# esp32-hanover-flipdot.net
KiCad netlist of a schematic drawn in EAGLE
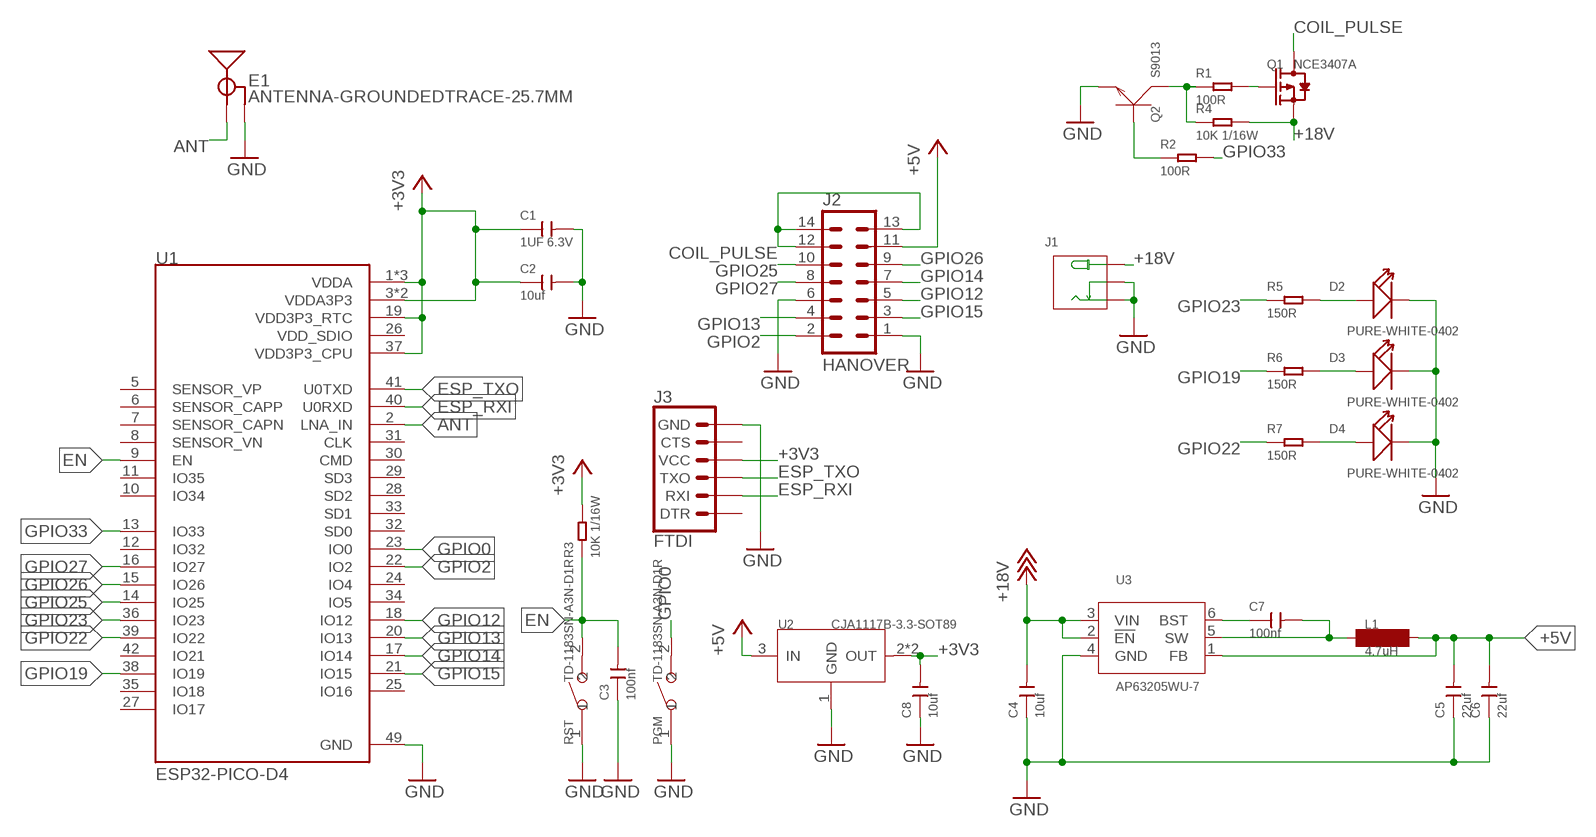
[diagram p0: schematic, sheet 1]

(export (version "E")
  (design (tool "Eeschema 10.0.6"))
  (components
    (comp (ref "C1")
      (value "1UF 6.3V")
      (footprint "eagle-import:C0402")
      (fields (field (name "MPN") "CC0402KRX5R5BB105"))
      (libsource (lib "eagle-import") (part "CERAMIC-1UF-6.3V-10%-X5R(0402)"))
    )
    (comp (ref "C2")
      (value "10uf")
      (footprint "eagle-import:C0402")
      (fields (field (name "MPN") "CC0402MRX5R5BB106"))
      (libsource (lib "eagle-import") (part "CERAMIC-10UF-6.3V-20%-X5R(0402)"))
    )
    (comp (ref "C3")
      (value "100nf")
      (footprint "eagle-import:C0402")
      (fields (field (name "MPN") "CC0402KRX7R8BB104"))
      (libsource (lib "eagle-import") (part "CERAMIC-100NF-25V-10%-X7R(0402)"))
    )
    (comp (ref "C4")
      (value "10uf")
      (footprint "eagle-import:C0805")
      (fields (field (name "MPN") "CC0805KKX5R8BB106"))
      (libsource (lib "eagle-import") (part "CERAMIC-10UF-25V-10%-X5R(0805)"))
    )
    (comp (ref "C5")
      (value "22uf")
      (footprint "eagle-import:C0805")
      (fields (field (name "MPN") "CC0805MKX5R5BB226"))
      (libsource (lib "eagle-import") (part "CERAMIC-22UF-6.3V-20%-X5R(0805)"))
    )
    (comp (ref "C6")
      (value "22uf")
      (footprint "eagle-import:C0805")
      (fields (field (name "MPN") "CC0805MKX5R5BB226"))
      (libsource (lib "eagle-import") (part "CERAMIC-22UF-6.3V-20%-X5R(0805)"))
    )
    (comp (ref "C7")
      (value "100nf")
      (footprint "eagle-import:C0402")
      (fields (field (name "MPN") "CC0402KRX7R8BB104"))
      (libsource (lib "eagle-import") (part "CERAMIC-100NF-25V-10%-X7R(0402)"))
    )
    (comp (ref "C8")
      (value "10uf")
      (footprint "eagle-import:C0402")
      (fields (field (name "MPN") "CC0402MRX5R5BB106"))
      (libsource (lib "eagle-import") (part "CERAMIC-10UF-6.3V-20%-X5R(0402)"))
    )
    (comp (ref "D2")
      (value "PURE-WHITE-0402")
      (footprint "eagle-import:LED-0402")
      (fields (field (name "MPN") "16-219A/T2D-AR2T1QY/3T"))
      (libsource (lib "eagle-import") (part "SMD-LED-YELLOW-DIFFUSED-PURE-WHITE(0402)"))
    )
    (comp (ref "D3")
      (value "PURE-WHITE-0402")
      (footprint "eagle-import:LED-0402")
      (fields (field (name "MPN") "16-219A/T2D-AR2T1QY/3T"))
      (libsource (lib "eagle-import") (part "SMD-LED-YELLOW-DIFFUSED-PURE-WHITE(0402)"))
    )
    (comp (ref "D4")
      (value "PURE-WHITE-0402")
      (footprint "eagle-import:LED-0402")
      (fields (field (name "MPN") "16-219A/T2D-AR2T1QY/3T"))
      (libsource (lib "eagle-import") (part "SMD-LED-YELLOW-DIFFUSED-PURE-WHITE(0402)"))
    )
    (comp (ref "E1")
      (value "ANTENNA-GROUNDEDTRACE-25.7MM")
      (footprint "eagle-import:TRACE_ANTENNA_2.4GHZ_25.7MM")
      (libsource (lib "eagle-import") (part "ANTENNA-GROUNDEDTRACE-25.7MM"))
    )
    (comp (ref "J1")
      (value "DC-005")
      (footprint "eagle-import:3P-L14.2_W11.0_H9.0MM")
      (libsource (lib "eagle-import") (part "JACK-DC-005'DC-005'"))
    )
    (comp (ref "J2")
      (value "HANOVER")
      (footprint "eagle-import:ML14")
      (libsource (lib "eagle-import") (part "ML14"))
    )
    (comp (ref "J3")
      (value "FTDI")
      (footprint "eagle-import:6_PIN_SERIAL_TARGET_SIDE_W_SILK")
      (libsource (lib "eagle-import") (part "6_PIN_SERIAL_TARGETSILK"))
    )
    (comp (ref "L1")
      (value "4.7uH")
      (footprint "eagle-import:INDC2016X100N")
      (fields (field (name "TOLERANCE") "20%"))
      (libsource (lib "eagle-import") (part "VLS201610HBX-4R7M-1"))
    )
    (comp (ref "PGM")
      (value "TD-1183SN-A3N-D1R")
      (footprint "eagle-import:SW2-2.6-3.0X2.5X1.2+0.4MM")
      (fields (field (name "MPN") "B3U-1000P-2P-SMD"))
      (libsource (lib "eagle-import") (part "SMD-BUTTON(2P-3.0X2.5X1.2+0.4MM)-B3U-1000P-2P-SMD"))
    )
    (comp (ref "Q1")
      (value "NCE3407A")
      (footprint "eagle-import:SOT-23")
      (libsource (lib "eagle-import") (part "SMD-MOSFET-P-CH-VDC=30V-ID=4.3A-NCE3407A(SOT-23)"))
    )
    (comp (ref "Q2")
      (value "S9013")
      (footprint "eagle-import:SOT-23")
      (libsource (lib "eagle-import") (part "SMD-TRANSISTORS-NPN-25V-500MA-S9013(SOT-23)"))
    )
    (comp (ref "R1")
      (value "100R")
      (footprint "eagle-import:R0402")
      (fields (field (name "MPN") "RC0402JR-07100RL"))
      (libsource (lib "eagle-import") (part "SMD-RES-100R-5%-1/16W(0402)"))
    )
    (comp (ref "R2")
      (value "100R")
      (footprint "eagle-import:R0402")
      (fields (field (name "MPN") "RC0402JR-07100RL"))
      (libsource (lib "eagle-import") (part "SMD-RES-100R-5%-1/16W(0402)"))
    )
    (comp (ref "R3")
      (value "10K 1/16W")
      (footprint "eagle-import:R0402")
      (fields (field (name "MPN") "RC0402FR-0710KL"))
      (libsource (lib "eagle-import") (part "SMD-RES-10K-1%-1/16W(0402)"))
    )
    (comp (ref "R4")
      (value "10K 1/16W")
      (footprint "eagle-import:R0402")
      (fields (field (name "MPN") "RC0402FR-0710KL"))
      (libsource (lib "eagle-import") (part "SMD-RES-10K-1%-1/16W(0402)"))
    )
    (comp (ref "R5")
      (value "150R")
      (footprint "eagle-import:R0402")
      (fields (field (name "MPN") "RC0402JR-070RL") (field (name "MPN_1") "RC0402FR-07150RL"))
      (libsource (lib "eagle-import") (part "SMD-RES-150R-1%-1/16W(0402)"))
    )
    (comp (ref "R6")
      (value "150R")
      (footprint "eagle-import:R0402")
      (fields (field (name "MPN") "RC0402JR-070RL") (field (name "MPN_1") "RC0402FR-07150RL"))
      (libsource (lib "eagle-import") (part "SMD-RES-150R-1%-1/16W(0402)"))
    )
    (comp (ref "R7")
      (value "150R")
      (footprint "eagle-import:R0402")
      (fields (field (name "MPN") "RC0402JR-070RL") (field (name "MPN_1") "RC0402FR-07150RL"))
      (libsource (lib "eagle-import") (part "SMD-RES-150R-1%-1/16W(0402)"))
    )
    (comp (ref "RST")
      (value "TD-1183SN-A3N-D1R")
      (footprint "eagle-import:SW2-2.6-3.0X2.5X1.2+0.4MM")
      (fields (field (name "MPN") "B3U-1000P-2P-SMD"))
      (libsource (lib "eagle-import") (part "SMD-BUTTON(2P-3.0X2.5X1.2+0.4MM)-B3U-1000P-2P-SMD"))
    )
    (comp (ref "U1")
      (value "ESP32-PICO-D4")
      (footprint "eagle-import:PQFN50P700X700X104-49N")
      (fields (field (name "MF") "Espressif Systems"))
      (libsource (lib "eagle-import") (part "ESP32-PICO-D4"))
    )
    (comp (ref "U2")
      (value "CJA1117B-3.3-SOT89")
      (footprint "eagle-import:SOT-89")
      (fields (field (name "MPN") "CJA1117B-3.3"))
      (libsource (lib "eagle-import") (part "PMIC-CJA1117B-3.3(SOT-89)"))
    )
    (comp (ref "U3")
      (value "AP63205WU-7")
      (footprint "eagle-import:SOT95P280X100-6N")
      (libsource (lib "eagle-import") (part "AP63205WU-7"))
    )
  )
  (nets
    (net (code "1") (name "+3V3") (class "Default")
      (node (ref "C1") (pin "1") (pinfunction "1_1") (pintype "passive"))
      (node (ref "C2") (pin "1") (pinfunction "1_1") (pintype "passive"))
      (node (ref "C8") (pin "2") (pinfunction "2_2") (pintype "passive"))
      (node (ref "J3") (pin "P$4") (pinfunction "VCC_P$4") (pintype "passive"))
      (node (ref "R3") (pin "2") (pinfunction "2_2") (pintype "passive"))
      (node (ref "U1") (pin "1") (pinfunction "VDDA_1") (pintype "power_in"))
      (node (ref "U1") (pin "19") (pinfunction "VDD3P3_RTC_19") (pintype "power_in"))
      (node (ref "U1") (pin "3") (pinfunction "VDDA3P3_3") (pintype "power_in"))
      (node (ref "U1") (pin "37") (pinfunction "VDD3P3_CPU_37") (pintype "power_in"))
      (node (ref "U1") (pin "4") (pinfunction "VDDA3P3_4") (pintype "power_in"))
      (node (ref "U1") (pin "43") (pinfunction "VDDA_43") (pintype "power_in"))
      (node (ref "U1") (pin "46") (pinfunction "VDDA_46") (pintype "power_in"))
      (node (ref "U2") (pin "2") (pinfunction "OUT_2") (pintype "bidirectional"))
      (node (ref "U2") (pin "4") (pinfunction "OUT_4") (pintype "bidirectional"))
    )
    (net (code "2") (name "+5V") (class "Default")
      (node (ref "C5") (pin "2") (pinfunction "2_2") (pintype "passive"))
      (node (ref "C6") (pin "2") (pinfunction "2_2") (pintype "passive"))
      (node (ref "J2") (pin "11") (pinfunction "11_11") (pintype "passive"))
      (node (ref "L1") (pin "2") (pinfunction "2_2") (pintype "passive"))
      (node (ref "U2") (pin "3") (pinfunction "IN_3") (pintype "bidirectional"))
      (node (ref "U3") (pin "1") (pinfunction "FB_1") (pintype "power_in"))
    )
    (net (code "3") (name "+18V") (class "Default")
      (node (ref "C4") (pin "2") (pinfunction "2_2") (pintype "passive"))
      (node (ref "J1") (pin "+B") (pinfunction "+_+B") (pintype "bidirectional"))
      (node (ref "J1") (pin "+T") (pinfunction "+_+T") (pintype "bidirectional"))
      (node (ref "Q1") (pin "2") (pinfunction "S_2") (pintype "passive"))
      (node (ref "R4") (pin "2") (pinfunction "2_2") (pintype "passive"))
      (node (ref "U3") (pin "2") (pinfunction "~{EN}_2") (pintype "input"))
      (node (ref "U3") (pin "3") (pinfunction "VIN_3") (pintype "power_in"))
    )
    (net (code "4") (name "/COIL_PULSE") (class "Default")
      (node (ref "J2") (pin "12") (pinfunction "12_12") (pintype "passive"))
      (node (ref "J2") (pin "13") (pinfunction "13_13") (pintype "passive"))
      (node (ref "J2") (pin "14") (pinfunction "14_14") (pintype "passive"))
      (node (ref "Q1") (pin "3") (pinfunction "D_3") (pintype "passive"))
    )
    (net (code "5") (name "/VDD_SDIO") (class "Default")
      (node (ref "U1") (pin "26") (pinfunction "VDD_SDIO_26") (pintype "power_in"))
    )
    (net (code "6") (name "ANT") (class "Default")
      (node (ref "E1") (pin "ANT") (pinfunction "SIGNAL_ANT") (pintype "bidirectional"))
      (node (ref "U1") (pin "2") (pinfunction "LNA_IN_2") (pintype "bidirectional"))
    )
    (net (code "7") (name "EN") (class "Default")
      (node (ref "C3") (pin "2") (pinfunction "2_2") (pintype "passive"))
      (node (ref "R3") (pin "1") (pinfunction "1_1") (pintype "passive"))
      (node (ref "RST") (pin "2") (pinfunction "2_2") (pintype "bidirectional"))
      (node (ref "U1") (pin "9") (pinfunction "EN_9") (pintype "input"))
    )
    (net (code "8") (name "ESP_RXI") (class "Default")
      (node (ref "J3") (pin "P$3") (pinfunction "RXI_P$3") (pintype "passive"))
      (node (ref "U1") (pin "40") (pinfunction "U0RXD_40") (pintype "bidirectional"))
    )
    (net (code "9") (name "ESP_TXO") (class "Default")
      (node (ref "J3") (pin "P$2") (pinfunction "TXO_P$2") (pintype "passive"))
      (node (ref "U1") (pin "41") (pinfunction "U0TXD_41") (pintype "bidirectional"))
    )
    (net (code "10") (name "GND") (class "Default")
      (node (ref "C1") (pin "2") (pinfunction "2_2") (pintype "passive"))
      (node (ref "C2") (pin "2") (pinfunction "2_2") (pintype "passive"))
      (node (ref "C3") (pin "1") (pinfunction "1_1") (pintype "passive"))
      (node (ref "C4") (pin "1") (pinfunction "1_1") (pintype "passive"))
      (node (ref "C5") (pin "1") (pinfunction "1_1") (pintype "passive"))
      (node (ref "C6") (pin "1") (pinfunction "1_1") (pintype "passive"))
      (node (ref "C8") (pin "1") (pinfunction "1_1") (pintype "passive"))
      (node (ref "D2") (pin "-") (pinfunction "-_-") (pintype "passive"))
      (node (ref "D3") (pin "-") (pinfunction "-_-") (pintype "passive"))
      (node (ref "D4") (pin "-") (pinfunction "-_-") (pintype "passive"))
      (node (ref "E1") (pin "GND") (pinfunction "GND_GND") (pintype "bidirectional"))
      (node (ref "E1") (pin "GND2") (pinfunction "GND_GND2") (pintype "bidirectional"))
      (node (ref "J1") (pin "-1B") (pinfunction "-_-1B") (pintype "bidirectional"))
      (node (ref "J1") (pin "-1T") (pinfunction "-_-1T") (pintype "bidirectional"))
      (node (ref "J1") (pin "-2B") (pinfunction "CDN_-2B") (pintype "bidirectional"))
      (node (ref "J1") (pin "-2T") (pinfunction "CDN_-2T") (pintype "bidirectional"))
      (node (ref "J2") (pin "1") (pinfunction "1_1") (pintype "passive"))
      (node (ref "J2") (pin "6") (pinfunction "6_6") (pintype "passive"))
      (node (ref "J3") (pin "P$6") (pinfunction "GND_P$6") (pintype "passive"))
      (node (ref "PGM") (pin "1") (pinfunction "1_1") (pintype "bidirectional"))
      (node (ref "Q2") (pin "2") (pinfunction "E_2") (pintype "passive"))
      (node (ref "RST") (pin "1") (pinfunction "1_1") (pintype "bidirectional"))
      (node (ref "U1") (pin "49") (pinfunction "GND_49") (pintype "power_in"))
      (node (ref "U2") (pin "1") (pinfunction "GND_1") (pintype "bidirectional"))
      (node (ref "U3") (pin "4") (pinfunction "GND_4") (pintype "power_in"))
    )
    (net (code "11") (name "GPIO0") (class "Default")
      (node (ref "PGM") (pin "2") (pinfunction "2_2") (pintype "bidirectional"))
      (node (ref "U1") (pin "23") (pinfunction "IO0_23") (pintype "bidirectional"))
    )
    (net (code "12") (name "GPIO2") (class "Default")
      (node (ref "J2") (pin "2") (pinfunction "2_2") (pintype "passive"))
      (node (ref "U1") (pin "22") (pinfunction "IO2_22") (pintype "bidirectional"))
    )
    (net (code "13") (name "GPIO12") (class "Default")
      (node (ref "J2") (pin "5") (pinfunction "5_5") (pintype "passive"))
      (node (ref "U1") (pin "18") (pinfunction "IO12_18") (pintype "bidirectional"))
    )
    (net (code "14") (name "GPIO13") (class "Default")
      (node (ref "J2") (pin "4") (pinfunction "4_4") (pintype "passive"))
      (node (ref "U1") (pin "20") (pinfunction "IO13_20") (pintype "bidirectional"))
    )
    (net (code "15") (name "GPIO14") (class "Default")
      (node (ref "J2") (pin "7") (pinfunction "7_7") (pintype "passive"))
      (node (ref "U1") (pin "17") (pinfunction "IO14_17") (pintype "bidirectional"))
    )
    (net (code "16") (name "GPIO15") (class "Default")
      (node (ref "J2") (pin "3") (pinfunction "3_3") (pintype "passive"))
      (node (ref "U1") (pin "21") (pinfunction "IO15_21") (pintype "bidirectional"))
    )
    (net (code "17") (name "GPIO19") (class "Default")
      (node (ref "R6") (pin "1") (pinfunction "1_1") (pintype "passive"))
      (node (ref "U1") (pin "38") (pinfunction "IO19_38") (pintype "bidirectional"))
    )
    (net (code "18") (name "GPIO22") (class "Default")
      (node (ref "R7") (pin "1") (pinfunction "1_1") (pintype "passive"))
      (node (ref "U1") (pin "39") (pinfunction "IO22_39") (pintype "bidirectional"))
    )
    (net (code "19") (name "GPIO23") (class "Default")
      (node (ref "R5") (pin "1") (pinfunction "1_1") (pintype "passive"))
      (node (ref "U1") (pin "36") (pinfunction "IO23_36") (pintype "bidirectional"))
    )
    (net (code "20") (name "GPIO25") (class "Default")
      (node (ref "J2") (pin "10") (pinfunction "10_10") (pintype "passive"))
      (node (ref "U1") (pin "14") (pinfunction "IO25_14") (pintype "bidirectional"))
    )
    (net (code "21") (name "GPIO26") (class "Default")
      (node (ref "J2") (pin "9") (pinfunction "9_9") (pintype "passive"))
      (node (ref "U1") (pin "15") (pinfunction "IO26_15") (pintype "bidirectional"))
    )
    (net (code "22") (name "GPIO27") (class "Default")
      (node (ref "J2") (pin "8") (pinfunction "8_8") (pintype "passive"))
      (node (ref "U1") (pin "16") (pinfunction "IO27_16") (pintype "bidirectional"))
    )
    (net (code "23") (name "GPIO33") (class "Default")
      (node (ref "R2") (pin "2") (pinfunction "2_2") (pintype "passive"))
      (node (ref "U1") (pin "13") (pinfunction "IO33_13") (pintype "bidirectional"))
    )
    (net (code "24") (name "Net-(D2-Pad+)") (class "Default")
      (node (ref "D2") (pin "+") (pinfunction "+_+") (pintype "passive"))
      (node (ref "R5") (pin "2") (pinfunction "2_2") (pintype "passive"))
    )
    (net (code "25") (name "Net-(D3-Pad+)") (class "Default")
      (node (ref "D3") (pin "+") (pinfunction "+_+") (pintype "passive"))
      (node (ref "R6") (pin "2") (pinfunction "2_2") (pintype "passive"))
    )
    (net (code "26") (name "Net-(D4-Pad+)") (class "Default")
      (node (ref "D4") (pin "+") (pinfunction "+_+") (pintype "passive"))
      (node (ref "R7") (pin "2") (pinfunction "2_2") (pintype "passive"))
    )
    (net (code "27") (name "Net-(Q1-G)") (class "Default")
      (node (ref "Q1") (pin "1") (pinfunction "G_1") (pintype "passive"))
      (node (ref "R1") (pin "2") (pinfunction "2_2") (pintype "passive"))
    )
    (net (code "28") (name "Net-(Q2-B)") (class "Default")
      (node (ref "Q2") (pin "1") (pinfunction "B_1") (pintype "passive"))
      (node (ref "R2") (pin "1") (pinfunction "1_1") (pintype "passive"))
    )
    (net (code "29") (name "Net-(Q2-C)") (class "Default")
      (node (ref "Q2") (pin "3") (pinfunction "C_3") (pintype "passive"))
      (node (ref "R1") (pin "1") (pinfunction "1_1") (pintype "passive"))
      (node (ref "R4") (pin "1") (pinfunction "1_1") (pintype "passive"))
    )
    (net (code "30") (name "Net-(U3-BST)") (class "Default")
      (node (ref "C7") (pin "1") (pinfunction "1_1") (pintype "passive"))
      (node (ref "U3") (pin "6") (pinfunction "BST_6") (pintype "bidirectional"))
    )
    (net (code "31") (name "Net-(U3-SW)") (class "Default")
      (node (ref "C7") (pin "2") (pinfunction "2_2") (pintype "passive"))
      (node (ref "L1") (pin "1") (pinfunction "1_1") (pintype "passive"))
      (node (ref "U3") (pin "5") (pinfunction "SW_5") (pintype "bidirectional"))
    )
    (net (code "32") (name "unconnected-(J3-CTS-PadP$5)") (class "Default")
      (node (ref "J3") (pin "P$5") (pinfunction "CTS_P$5") (pintype "passive"))
    )
    (net (code "33") (name "unconnected-(J3-DTR-PadP$1)") (class "Default")
      (node (ref "J3") (pin "P$1") (pinfunction "DTR_P$1") (pintype "passive"))
    )
    (net (code "34") (name "unconnected-(U1-CLK-Pad31)") (class "Default")
      (node (ref "U1") (pin "31") (pinfunction "CLK_31") (pintype "bidirectional"))
    )
    (net (code "35") (name "unconnected-(U1-CMD-Pad30)") (class "Default")
      (node (ref "U1") (pin "30") (pinfunction "CMD_30") (pintype "bidirectional"))
    )
    (net (code "36") (name "unconnected-(U1-IO4-Pad24)") (class "Default")
      (node (ref "U1") (pin "24") (pinfunction "IO4_24") (pintype "bidirectional"))
    )
    (net (code "37") (name "unconnected-(U1-IO5-Pad34)") (class "Default")
      (node (ref "U1") (pin "34") (pinfunction "IO5_34") (pintype "bidirectional"))
    )
    (net (code "38") (name "unconnected-(U1-IO16-Pad25)") (class "Default")
      (node (ref "U1") (pin "25") (pinfunction "IO16_25") (pintype "bidirectional"))
    )
    (net (code "39") (name "unconnected-(U1-IO17-Pad27)") (class "Default")
      (node (ref "U1") (pin "27") (pinfunction "IO17_27") (pintype "bidirectional"))
    )
    (net (code "40") (name "unconnected-(U1-IO18-Pad35)") (class "Default")
      (node (ref "U1") (pin "35") (pinfunction "IO18_35") (pintype "bidirectional"))
    )
    (net (code "41") (name "unconnected-(U1-IO21-Pad42)") (class "Default")
      (node (ref "U1") (pin "42") (pinfunction "IO21_42") (pintype "bidirectional"))
    )
    (net (code "42") (name "unconnected-(U1-IO32-Pad12)") (class "Default")
      (node (ref "U1") (pin "12") (pinfunction "IO32_12") (pintype "bidirectional"))
    )
    (net (code "43") (name "unconnected-(U1-IO34-Pad10)") (class "Default")
      (node (ref "U1") (pin "10") (pinfunction "IO34_10") (pintype "input"))
    )
    (net (code "44") (name "unconnected-(U1-IO35-Pad11)") (class "Default")
      (node (ref "U1") (pin "11") (pinfunction "IO35_11") (pintype "input"))
    )
    (net (code "45") (name "unconnected-(U1-SD0-Pad32)") (class "Default")
      (node (ref "U1") (pin "32") (pinfunction "SD0_32") (pintype "bidirectional"))
    )
    (net (code "46") (name "unconnected-(U1-SD1-Pad33)") (class "Default")
      (node (ref "U1") (pin "33") (pinfunction "SD1_33") (pintype "bidirectional"))
    )
    (net (code "47") (name "unconnected-(U1-SD2-Pad28)") (class "Default")
      (node (ref "U1") (pin "28") (pinfunction "SD2_28") (pintype "bidirectional"))
    )
    (net (code "48") (name "unconnected-(U1-SD3-Pad29)") (class "Default")
      (node (ref "U1") (pin "29") (pinfunction "SD3_29") (pintype "bidirectional"))
    )
    (net (code "49") (name "unconnected-(U1-SENSOR_CAPN-Pad7)") (class "Default")
      (node (ref "U1") (pin "7") (pinfunction "SENSOR_CAPN_7") (pintype "input"))
    )
    (net (code "50") (name "unconnected-(U1-SENSOR_CAPP-Pad6)") (class "Default")
      (node (ref "U1") (pin "6") (pinfunction "SENSOR_CAPP_6") (pintype "input"))
    )
    (net (code "51") (name "unconnected-(U1-SENSOR_VN-Pad8)") (class "Default")
      (node (ref "U1") (pin "8") (pinfunction "SENSOR_VN_8") (pintype "input"))
    )
    (net (code "52") (name "unconnected-(U1-SENSOR_VP-Pad5)") (class "Default")
      (node (ref "U1") (pin "5") (pinfunction "SENSOR_VP_5") (pintype "input"))
    )
  )
)
